# Altera_ArriaGX_PCIExpress.net
KiCad netlist of a schematic drawn in Altium Designer
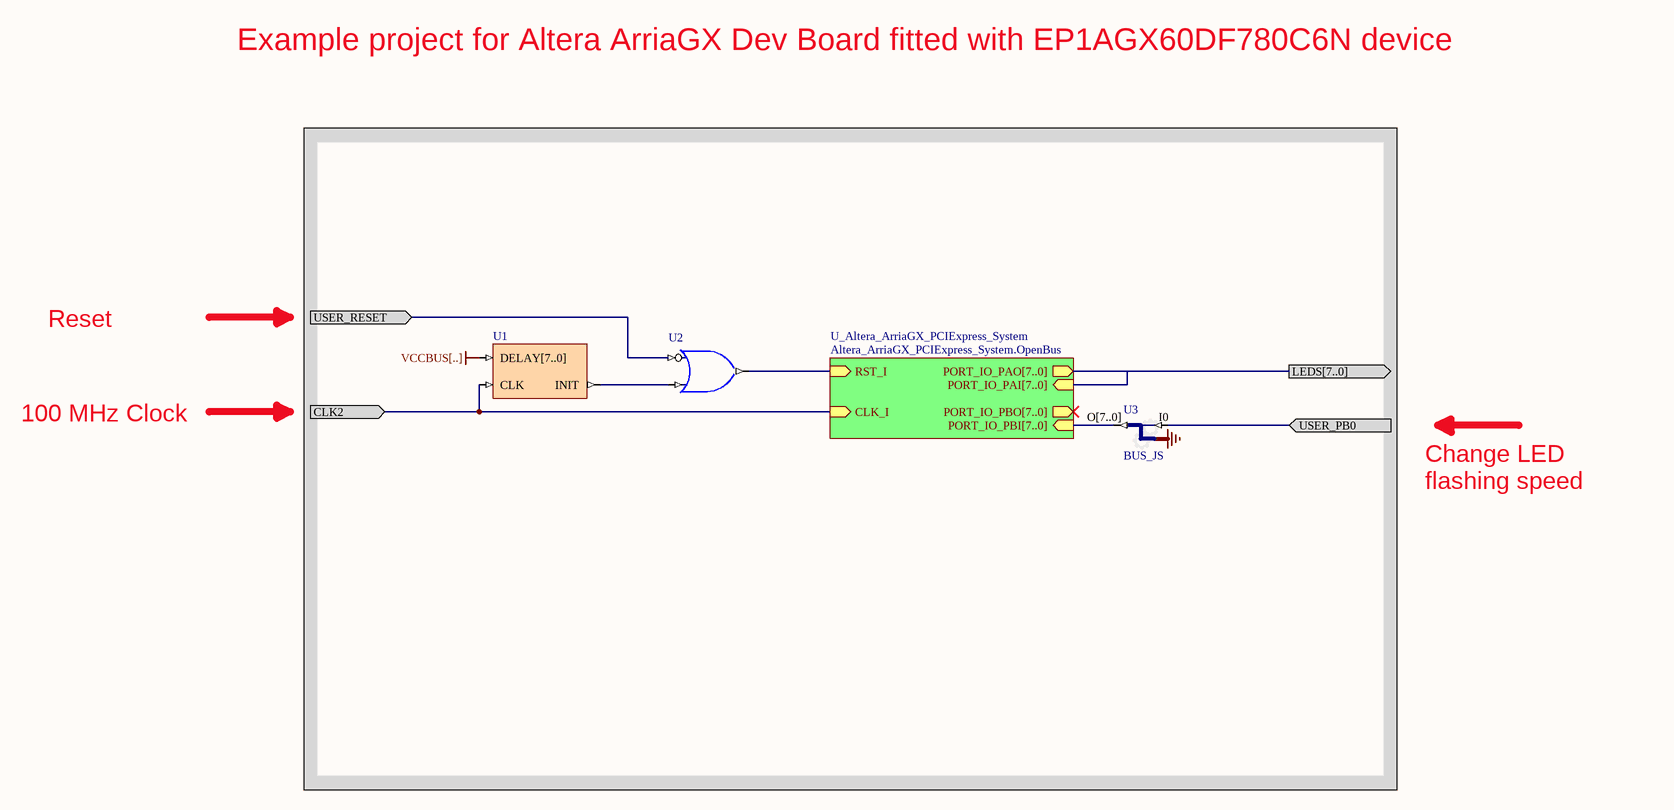
[diagram p0: Altera_ArriaGX_PCIExpress.SchDoc]

(export (version "E")
  (design (tool "Eeschema 10.0.6"))
  (components
    (comp (ref "U1")
      (value "FPGA_STARTUP8")
      (description "FPGA Startup With 8 Bit Delay")
      (fields (field (name "PUBLISHER") "Altium Limited"))
      (libsource (lib "FPGA Peripherals") (part "FPGA_STARTUP8"))
    )
    (comp (ref "U2")
      (value "OR2N1S")
      (description "2-Input OR Gate with Active Low A Input, Single Pin Version")
      (fields (field (name "PUBLISHER") "Altium Limited"))
      (libsource (lib "FPGA Generic") (part "OR2N1S"))
    )
    (comp (ref "U3")
      (value "BUS_JS")
      (description "Configurable Bus Joiner/Splitter")
      (fields (field (name "PUBLISHER") "Altium Limited"))
      (libsource (lib "FPGA Configurable Generic") (part "BUS_JS"))
    )
  )
  (nets
    (net (code "9") (name "/CLK2") (class "Default")
      (node (ref "U1") (pin "CLK") (pinfunction "CLK_CLK") (pintype "input"))
    )
    (net (code "12") (name "/PORT_IO_PBI[7..0]") (class "Default")
      (node (ref "U3") (pin "O[7..0]") (pinfunction "O[7..0]_O[7..0]") (pintype "output"))
    )
    (net (code "14") (name "/RST_I") (class "Default")
      (node (ref "U2") (pin "O") (pinfunction "O_O") (pintype "output"))
    )
    (net (code "15") (name "/USER_PB0") (class "Default")
      (node (ref "U3") (pin "I0") (pinfunction "I0_I0") (pintype "input"))
    )
    (net (code "16") (name "/USER_RESET") (class "Default")
      (node (ref "U2") (pin "I0") (pinfunction "I0_I0") (pintype "input"))
    )
    (net (code "17") (name "Net-(U1-PadINIT)") (class "Default")
      (node (ref "U1") (pin "INIT") (pinfunction "INIT_INIT") (pintype "output"))
      (node (ref "U2") (pin "I1") (pinfunction "I1_I1") (pintype "input"))
    )
    (net (code "18") (name "VCCBUS[..]") (class "Default")
      (node (ref "U1") (pin "DELAY[7..0]") (pinfunction "DELAY[7..0]_DELAY[7..0]") (pintype "input"))
    )
    (net (code "19") (name "unconnected-(U3-PadI1_B[6..0])") (class "Default")
      (node (ref "U3") (pin "I1_B[6..0]") (pinfunction "I1_B[6..0]_I1_B[6..0]") (pintype "input"))
    )
  )
)
